# scienceWing.net
KiCad netlist of a schematic drawn in EAGLE
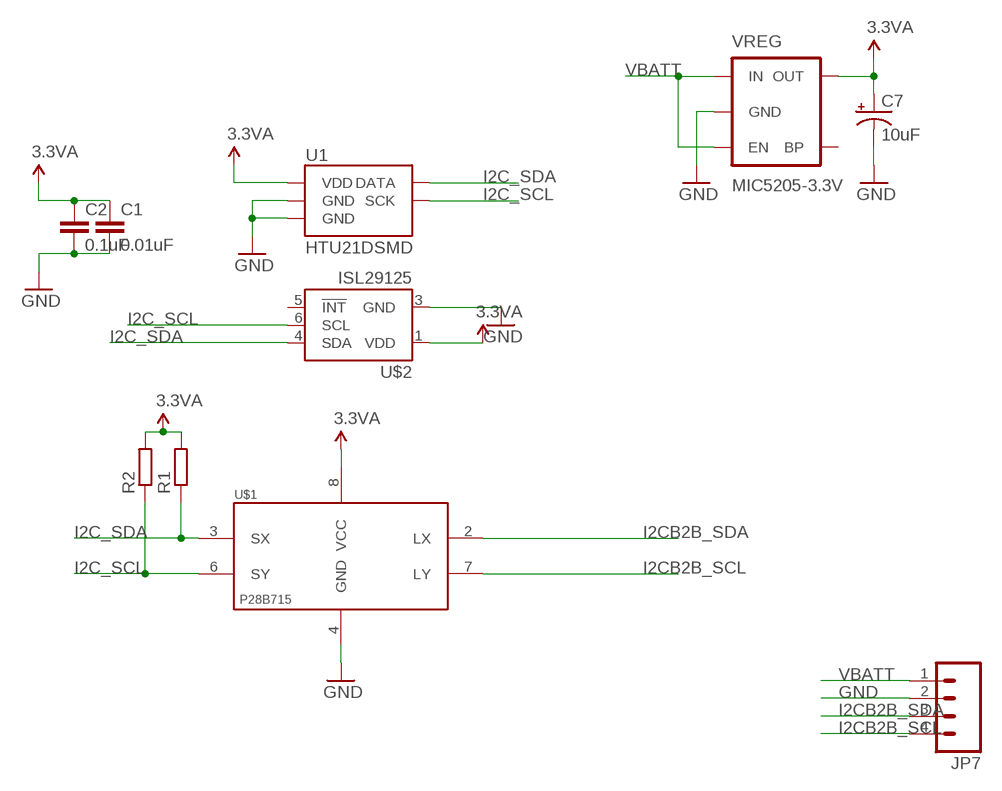
[diagram p0: schematic, sheet 1]

(export (version "E")
  (design (tool "Eeschema 10.0.6"))
  (components
    (comp (ref "C1")
      (value "0.01uF")
      (footprint "eagle-import:C0603")
      (libsource (lib "eagle-import") (part "C0603"))
    )
    (comp (ref "C2")
      (value "0.1uF")
      (footprint "eagle-import:C0603")
      (libsource (lib "eagle-import") (part "C0603"))
    )
    (comp (ref "C7")
      (value "10uF")
      (footprint "eagle-import:EIA3216")
      (libsource (lib "eagle-import") (part "CAP_POL1206"))
    )
    (comp (ref "JP7")
      (value "M04JST")
      (footprint "eagle-import:1X04-1.5MM_JST")
      (libsource (lib "eagle-import") (part "M04JST"))
    )
    (comp (ref "R1")
      (value "R0603")
      (footprint "eagle-import:R0603")
      (libsource (lib "eagle-import") (part "R0603"))
    )
    (comp (ref "R2")
      (value "R0603")
      (footprint "eagle-import:R0603")
      (libsource (lib "eagle-import") (part "R0603"))
    )
    (comp (ref "U$1")
      (value "P82B715")
      (footprint "eagle-import:SO8")
      (libsource (lib "eagle-import") (part "P82B715"))
    )
    (comp (ref "U$2")
      (value "ISL29125")
      (footprint "eagle-import:ODFN-LD-6")
      (libsource (lib "eagle-import") (part "ISL29125"))
    )
    (comp (ref "U1")
      (value "HTU21DSMD")
      (footprint "eagle-import:HTU21D")
      (libsource (lib "eagle-import") (part "HTU21DSMD"))
    )
    (comp (ref "VREG")
      (value "MIC5205-3.3V")
      (footprint "eagle-import:SOT23-5")
      (libsource (lib "eagle-import") (part "V_REG_LDOSMD"))
    )
  )
  (nets
    (net (code "1") (name "/I2CB2B_SCL") (class "Default")
      (node (ref "JP7") (pin "4") (pinfunction "4_4") (pintype "passive"))
      (node (ref "U$1") (pin "7") (pinfunction "LY_7") (pintype "bidirectional"))
    )
    (net (code "2") (name "/I2CB2B_SDA") (class "Default")
      (node (ref "JP7") (pin "3") (pinfunction "3_3") (pintype "passive"))
      (node (ref "U$1") (pin "2") (pinfunction "LX_2") (pintype "bidirectional"))
    )
    (net (code "3") (name "/I2C_SCL") (class "Default")
      (node (ref "R2") (pin "1") (pinfunction "1_1") (pintype "passive"))
      (node (ref "U$1") (pin "6") (pinfunction "SY_6") (pintype "bidirectional"))
      (node (ref "U$2") (pin "6") (pinfunction "SCL_6") (pintype "bidirectional"))
      (node (ref "U1") (pin "SCK") (pinfunction "SCK_SCK") (pintype "input"))
    )
    (net (code "4") (name "/I2C_SDA") (class "Default")
      (node (ref "R1") (pin "1") (pinfunction "1_1") (pintype "passive"))
      (node (ref "U$1") (pin "3") (pinfunction "SX_3") (pintype "bidirectional"))
      (node (ref "U$2") (pin "4") (pinfunction "SDA_4") (pintype "bidirectional"))
      (node (ref "U1") (pin "DATA") (pinfunction "DATA_DATA") (pintype "bidirectional"))
    )
    (net (code "5") (name "/VBATT") (class "Default")
      (node (ref "JP7") (pin "1") (pinfunction "1_1") (pintype "passive"))
      (node (ref "VREG") (pin "1") (pinfunction "IN_1") (pintype "input"))
      (node (ref "VREG") (pin "3") (pinfunction "EN_3") (pintype "input"))
    )
    (net (code "6") (name "3.3VA") (class "Default")
      (node (ref "C1") (pin "1") (pinfunction "1_1") (pintype "passive"))
      (node (ref "C2") (pin "1") (pinfunction "1_1") (pintype "passive"))
      (node (ref "C7") (pin "A") (pinfunction "+_A") (pintype "passive"))
      (node (ref "R1") (pin "2") (pinfunction "2_2") (pintype "passive"))
      (node (ref "R2") (pin "2") (pinfunction "2_2") (pintype "passive"))
      (node (ref "U$1") (pin "8") (pinfunction "VCC_8") (pintype "bidirectional"))
      (node (ref "U$2") (pin "1") (pinfunction "VDD_1") (pintype "bidirectional"))
      (node (ref "U1") (pin "VDD") (pinfunction "VDD_VDD") (pintype "power_in"))
      (node (ref "VREG") (pin "5") (pinfunction "OUT_5") (pintype "passive"))
    )
    (net (code "7") (name "GND") (class "Default")
      (node (ref "C1") (pin "2") (pinfunction "2_2") (pintype "passive"))
      (node (ref "C2") (pin "2") (pinfunction "2_2") (pintype "passive"))
      (node (ref "C7") (pin "C") (pinfunction "-_C") (pintype "passive"))
      (node (ref "JP7") (pin "2") (pinfunction "2_2") (pintype "passive"))
      (node (ref "U$1") (pin "4") (pinfunction "GND_4") (pintype "bidirectional"))
      (node (ref "U$2") (pin "3") (pinfunction "GND_3") (pintype "bidirectional"))
      (node (ref "U1") (pin "7") (pinfunction "GND_7") (pintype "power_in"))
      (node (ref "U1") (pin "GND") (pinfunction "GND_GND") (pintype "power_in"))
      (node (ref "VREG") (pin "2") (pinfunction "GND_2") (pintype "input"))
    )
    (net (code "8") (name "unconnected-(U$2-~{INT}-Pad5)") (class "Default")
      (node (ref "U$2") (pin "5") (pinfunction "~{INT}_5") (pintype "bidirectional"))
    )
    (net (code "9") (name "unconnected-(VREG-BP-Pad4)") (class "Default")
      (node (ref "VREG") (pin "4") (pinfunction "BP_4") (pintype "input"))
    )
  )
)
